# BitUDCounter.net
KiCad netlist of a schematic drawn in EAGLE
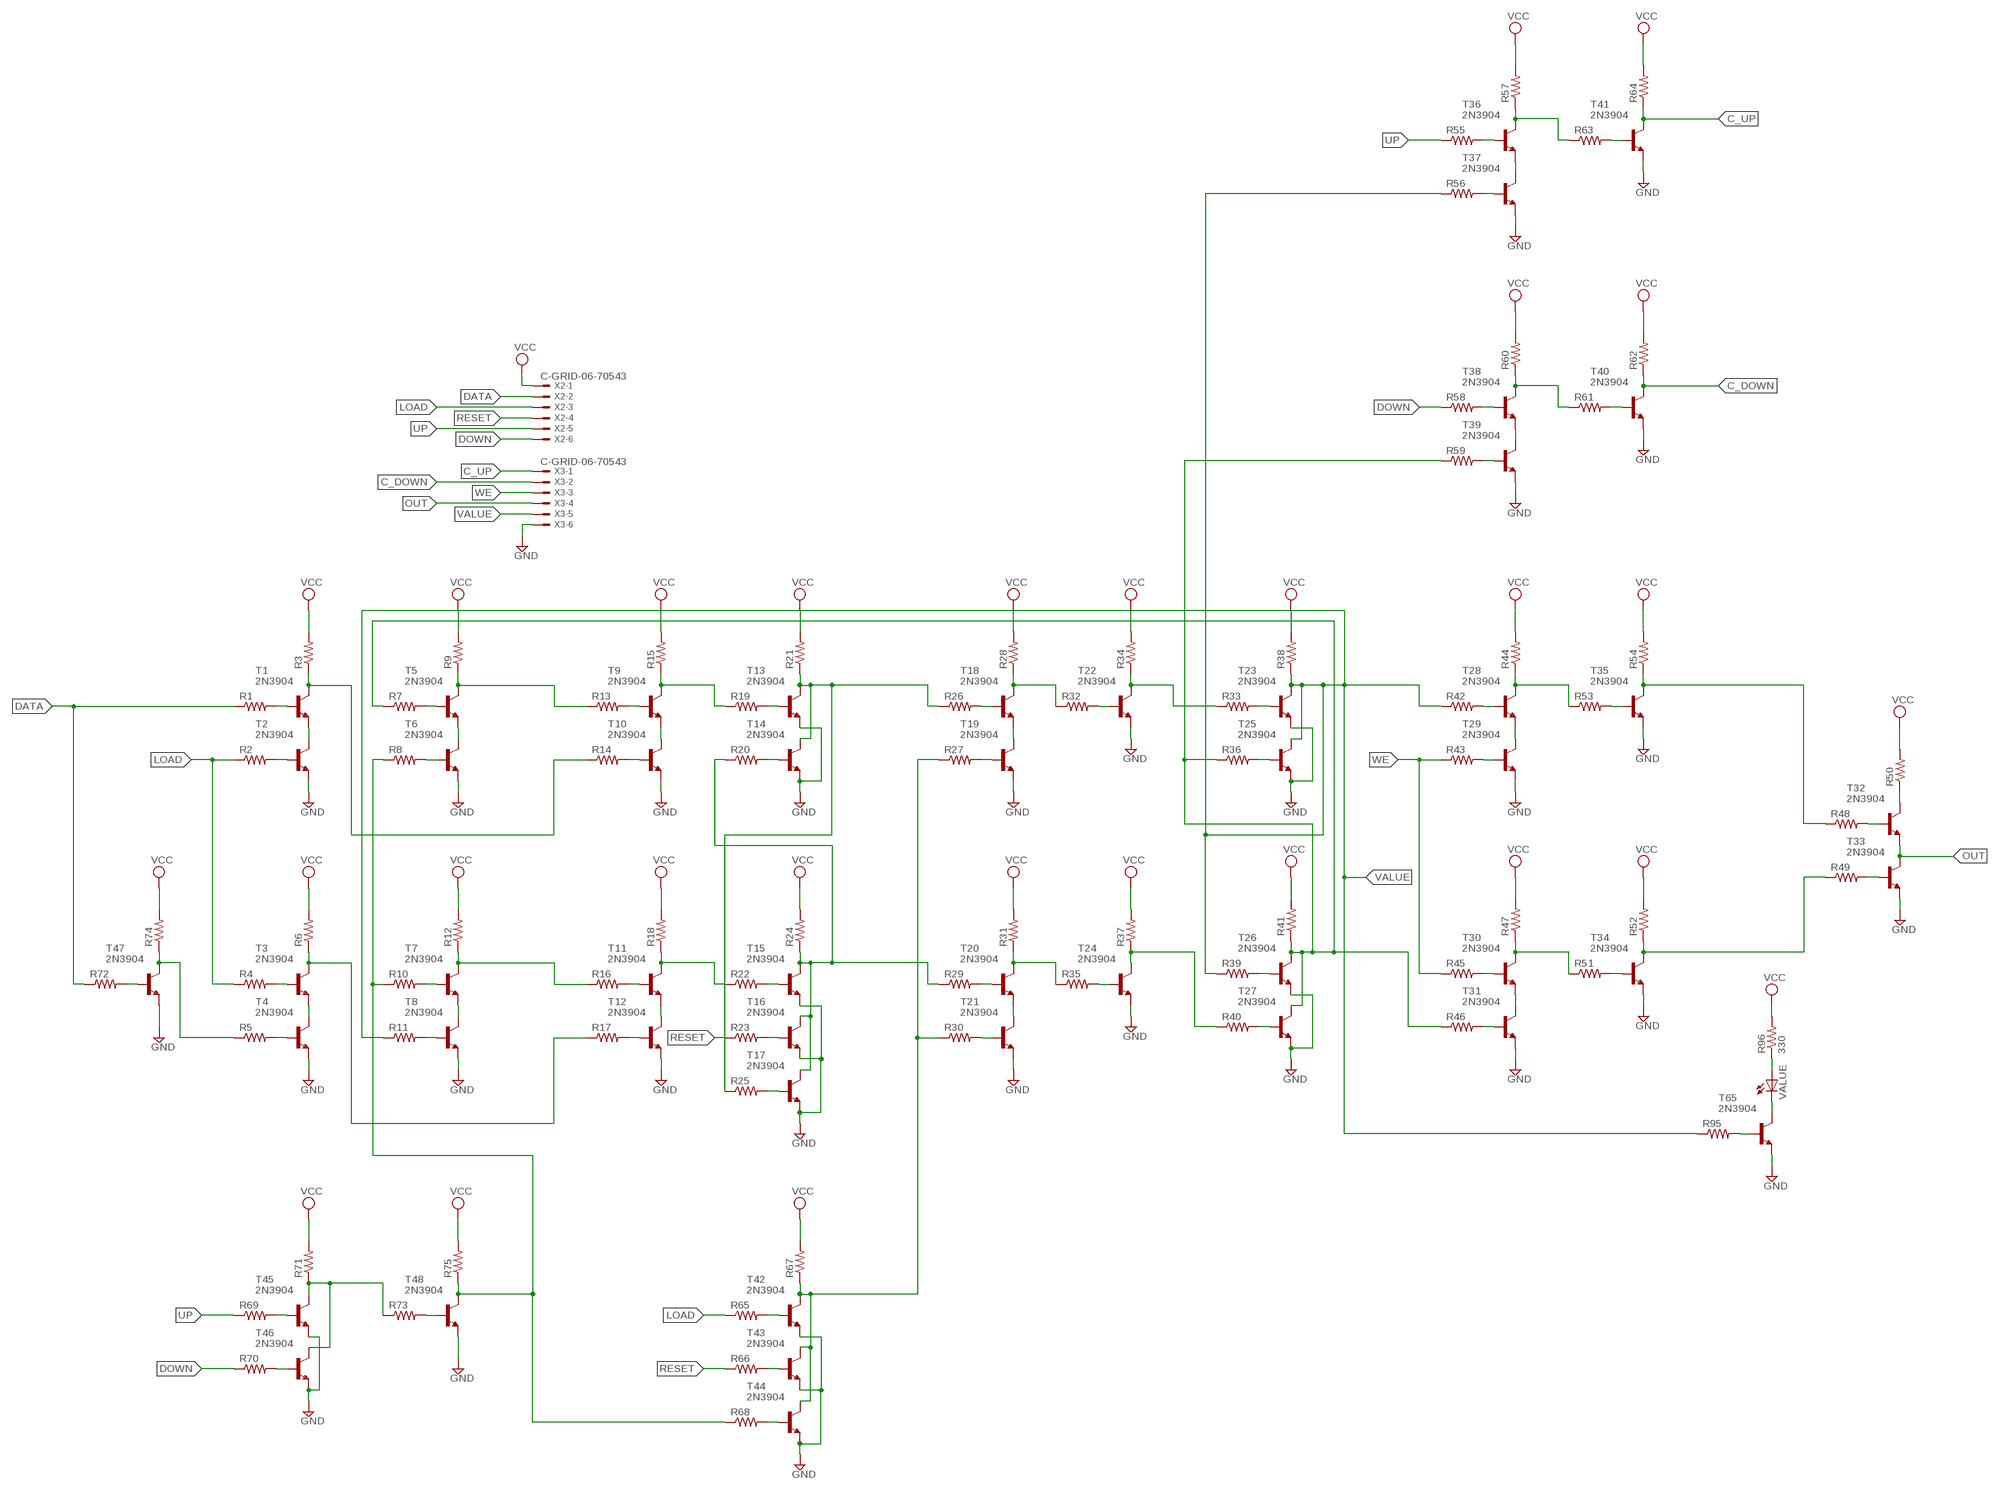
[diagram p0: schematic, sheet 1]

(export (version "E")
  (design (tool "Eeschema 10.0.6"))
  (components
    (comp (ref "R1")
      (value "R-US_0309/10")
      (footprint "eagle-import:0309_10")
      (libsource (lib "eagle-import") (part "R-US_0309/10"))
    )
    (comp (ref "R2")
      (value "R-US_0309/10")
      (footprint "eagle-import:0309_10")
      (libsource (lib "eagle-import") (part "R-US_0309/10"))
    )
    (comp (ref "R3")
      (value "R-US_0309/10")
      (footprint "eagle-import:0309_10")
      (libsource (lib "eagle-import") (part "R-US_0309/10"))
    )
    (comp (ref "R4")
      (value "R-US_0309/10")
      (footprint "eagle-import:0309_10")
      (libsource (lib "eagle-import") (part "R-US_0309/10"))
    )
    (comp (ref "R5")
      (value "R-US_0309/10")
      (footprint "eagle-import:0309_10")
      (libsource (lib "eagle-import") (part "R-US_0309/10"))
    )
    (comp (ref "R6")
      (value "R-US_0309/10")
      (footprint "eagle-import:0309_10")
      (libsource (lib "eagle-import") (part "R-US_0309/10"))
    )
    (comp (ref "R7")
      (value "R-US_0309/10")
      (footprint "eagle-import:0309_10")
      (libsource (lib "eagle-import") (part "R-US_0309/10"))
    )
    (comp (ref "R8")
      (value "R-US_0309/10")
      (footprint "eagle-import:0309_10")
      (libsource (lib "eagle-import") (part "R-US_0309/10"))
    )
    (comp (ref "R9")
      (value "R-US_0309/10")
      (footprint "eagle-import:0309_10")
      (libsource (lib "eagle-import") (part "R-US_0309/10"))
    )
    (comp (ref "R10")
      (value "R-US_0309/10")
      (footprint "eagle-import:0309_10")
      (libsource (lib "eagle-import") (part "R-US_0309/10"))
    )
    (comp (ref "R11")
      (value "R-US_0309/10")
      (footprint "eagle-import:0309_10")
      (libsource (lib "eagle-import") (part "R-US_0309/10"))
    )
    (comp (ref "R12")
      (value "R-US_0309/10")
      (footprint "eagle-import:0309_10")
      (libsource (lib "eagle-import") (part "R-US_0309/10"))
    )
    (comp (ref "R13")
      (value "R-US_0309/10")
      (footprint "eagle-import:0309_10")
      (libsource (lib "eagle-import") (part "R-US_0309/10"))
    )
    (comp (ref "R14")
      (value "R-US_0309/10")
      (footprint "eagle-import:0309_10")
      (libsource (lib "eagle-import") (part "R-US_0309/10"))
    )
    (comp (ref "R15")
      (value "R-US_0309/10")
      (footprint "eagle-import:0309_10")
      (libsource (lib "eagle-import") (part "R-US_0309/10"))
    )
    (comp (ref "R16")
      (value "R-US_0309/10")
      (footprint "eagle-import:0309_10")
      (libsource (lib "eagle-import") (part "R-US_0309/10"))
    )
    (comp (ref "R17")
      (value "R-US_0309/10")
      (footprint "eagle-import:0309_10")
      (libsource (lib "eagle-import") (part "R-US_0309/10"))
    )
    (comp (ref "R18")
      (value "R-US_0309/10")
      (footprint "eagle-import:0309_10")
      (libsource (lib "eagle-import") (part "R-US_0309/10"))
    )
    (comp (ref "R19")
      (value "R-US_0309/10")
      (footprint "eagle-import:0309_10")
      (libsource (lib "eagle-import") (part "R-US_0309/10"))
    )
    (comp (ref "R20")
      (value "R-US_0309/10")
      (footprint "eagle-import:0309_10")
      (libsource (lib "eagle-import") (part "R-US_0309/10"))
    )
    (comp (ref "R21")
      (value "R-US_0309/10")
      (footprint "eagle-import:0309_10")
      (libsource (lib "eagle-import") (part "R-US_0309/10"))
    )
    (comp (ref "R22")
      (value "R-US_0309/10")
      (footprint "eagle-import:0309_10")
      (libsource (lib "eagle-import") (part "R-US_0309/10"))
    )
    (comp (ref "R23")
      (value "R-US_0309/10")
      (footprint "eagle-import:0309_10")
      (libsource (lib "eagle-import") (part "R-US_0309/10"))
    )
    (comp (ref "R24")
      (value "R-US_0309/10")
      (footprint "eagle-import:0309_10")
      (libsource (lib "eagle-import") (part "R-US_0309/10"))
    )
    (comp (ref "R25")
      (value "R-US_0309/10")
      (footprint "eagle-import:0309_10")
      (libsource (lib "eagle-import") (part "R-US_0309/10"))
    )
    (comp (ref "R26")
      (value "R-US_0309/10")
      (footprint "eagle-import:0309_10")
      (libsource (lib "eagle-import") (part "R-US_0309/10"))
    )
    (comp (ref "R27")
      (value "R-US_0309/10")
      (footprint "eagle-import:0309_10")
      (libsource (lib "eagle-import") (part "R-US_0309/10"))
    )
    (comp (ref "R28")
      (value "R-US_0309/10")
      (footprint "eagle-import:0309_10")
      (libsource (lib "eagle-import") (part "R-US_0309/10"))
    )
    (comp (ref "R29")
      (value "R-US_0309/10")
      (footprint "eagle-import:0309_10")
      (libsource (lib "eagle-import") (part "R-US_0309/10"))
    )
    (comp (ref "R30")
      (value "R-US_0309/10")
      (footprint "eagle-import:0309_10")
      (libsource (lib "eagle-import") (part "R-US_0309/10"))
    )
    (comp (ref "R31")
      (value "R-US_0309/10")
      (footprint "eagle-import:0309_10")
      (libsource (lib "eagle-import") (part "R-US_0309/10"))
    )
    (comp (ref "R32")
      (value "R-US_0309/10")
      (footprint "eagle-import:0309_10")
      (libsource (lib "eagle-import") (part "R-US_0309/10"))
    )
    (comp (ref "R33")
      (value "R-US_0309/10")
      (footprint "eagle-import:0309_10")
      (libsource (lib "eagle-import") (part "R-US_0309/10"))
    )
    (comp (ref "R34")
      (value "R-US_0309/10")
      (footprint "eagle-import:0309_10")
      (libsource (lib "eagle-import") (part "R-US_0309/10"))
    )
    (comp (ref "R35")
      (value "R-US_0309/10")
      (footprint "eagle-import:0309_10")
      (libsource (lib "eagle-import") (part "R-US_0309/10"))
    )
    (comp (ref "R36")
      (value "R-US_0309/10")
      (footprint "eagle-import:0309_10")
      (libsource (lib "eagle-import") (part "R-US_0309/10"))
    )
    (comp (ref "R37")
      (value "R-US_0309/10")
      (footprint "eagle-import:0309_10")
      (libsource (lib "eagle-import") (part "R-US_0309/10"))
    )
    (comp (ref "R38")
      (value "R-US_0309/10")
      (footprint "eagle-import:0309_10")
      (libsource (lib "eagle-import") (part "R-US_0309/10"))
    )
    (comp (ref "R39")
      (value "R-US_0309/10")
      (footprint "eagle-import:0309_10")
      (libsource (lib "eagle-import") (part "R-US_0309/10"))
    )
    (comp (ref "R40")
      (value "R-US_0309/10")
      (footprint "eagle-import:0309_10")
      (libsource (lib "eagle-import") (part "R-US_0309/10"))
    )
    (comp (ref "R41")
      (value "R-US_0309/10")
      (footprint "eagle-import:0309_10")
      (libsource (lib "eagle-import") (part "R-US_0309/10"))
    )
    (comp (ref "R42")
      (value "R-US_0309/10")
      (footprint "eagle-import:0309_10")
      (libsource (lib "eagle-import") (part "R-US_0309/10"))
    )
    (comp (ref "R43")
      (value "R-US_0309/10")
      (footprint "eagle-import:0309_10")
      (libsource (lib "eagle-import") (part "R-US_0309/10"))
    )
    (comp (ref "R44")
      (value "R-US_0309/10")
      (footprint "eagle-import:0309_10")
      (libsource (lib "eagle-import") (part "R-US_0309/10"))
    )
    (comp (ref "R45")
      (value "R-US_0309/10")
      (footprint "eagle-import:0309_10")
      (libsource (lib "eagle-import") (part "R-US_0309/10"))
    )
    (comp (ref "R46")
      (value "R-US_0309/10")
      (footprint "eagle-import:0309_10")
      (libsource (lib "eagle-import") (part "R-US_0309/10"))
    )
    (comp (ref "R47")
      (value "R-US_0309/10")
      (footprint "eagle-import:0309_10")
      (libsource (lib "eagle-import") (part "R-US_0309/10"))
    )
    (comp (ref "R48")
      (value "R-US_0309/10")
      (footprint "eagle-import:0309_10")
      (libsource (lib "eagle-import") (part "R-US_0309/10"))
    )
    (comp (ref "R49")
      (value "R-US_0309/10")
      (footprint "eagle-import:0309_10")
      (libsource (lib "eagle-import") (part "R-US_0309/10"))
    )
    (comp (ref "R50")
      (value "R-US_0309/10")
      (footprint "eagle-import:0309_10")
      (libsource (lib "eagle-import") (part "R-US_0309/10"))
    )
    (comp (ref "R51")
      (value "R-US_0309/10")
      (footprint "eagle-import:0309_10")
      (libsource (lib "eagle-import") (part "R-US_0309/10"))
    )
    (comp (ref "R52")
      (value "R-US_0309/10")
      (footprint "eagle-import:0309_10")
      (libsource (lib "eagle-import") (part "R-US_0309/10"))
    )
    (comp (ref "R53")
      (value "R-US_0309/10")
      (footprint "eagle-import:0309_10")
      (libsource (lib "eagle-import") (part "R-US_0309/10"))
    )
    (comp (ref "R54")
      (value "R-US_0309/10")
      (footprint "eagle-import:0309_10")
      (libsource (lib "eagle-import") (part "R-US_0309/10"))
    )
    (comp (ref "R55")
      (value "R-US_0309/10")
      (footprint "eagle-import:0309_10")
      (libsource (lib "eagle-import") (part "R-US_0309/10"))
    )
    (comp (ref "R56")
      (value "R-US_0309/10")
      (footprint "eagle-import:0309_10")
      (libsource (lib "eagle-import") (part "R-US_0309/10"))
    )
    (comp (ref "R57")
      (value "R-US_0309/10")
      (footprint "eagle-import:0309_10")
      (libsource (lib "eagle-import") (part "R-US_0309/10"))
    )
    (comp (ref "R58")
      (value "R-US_0309/10")
      (footprint "eagle-import:0309_10")
      (libsource (lib "eagle-import") (part "R-US_0309/10"))
    )
    (comp (ref "R59")
      (value "R-US_0309/10")
      (footprint "eagle-import:0309_10")
      (libsource (lib "eagle-import") (part "R-US_0309/10"))
    )
    (comp (ref "R60")
      (value "R-US_0309/10")
      (footprint "eagle-import:0309_10")
      (libsource (lib "eagle-import") (part "R-US_0309/10"))
    )
    (comp (ref "R61")
      (value "R-US_0309/10")
      (footprint "eagle-import:0309_10")
      (libsource (lib "eagle-import") (part "R-US_0309/10"))
    )
    (comp (ref "R62")
      (value "R-US_0309/10")
      (footprint "eagle-import:0309_10")
      (libsource (lib "eagle-import") (part "R-US_0309/10"))
    )
    (comp (ref "R63")
      (value "R-US_0309/10")
      (footprint "eagle-import:0309_10")
      (libsource (lib "eagle-import") (part "R-US_0309/10"))
    )
    (comp (ref "R64")
      (value "R-US_0309/10")
      (footprint "eagle-import:0309_10")
      (libsource (lib "eagle-import") (part "R-US_0309/10"))
    )
    (comp (ref "R65")
      (value "R-US_0309/10")
      (footprint "eagle-import:0309_10")
      (libsource (lib "eagle-import") (part "R-US_0309/10"))
    )
    (comp (ref "R66")
      (value "R-US_0309/10")
      (footprint "eagle-import:0309_10")
      (libsource (lib "eagle-import") (part "R-US_0309/10"))
    )
    (comp (ref "R67")
      (value "R-US_0309/10")
      (footprint "eagle-import:0309_10")
      (libsource (lib "eagle-import") (part "R-US_0309/10"))
    )
    (comp (ref "R68")
      (value "R-US_0309/10")
      (footprint "eagle-import:0309_10")
      (libsource (lib "eagle-import") (part "R-US_0309/10"))
    )
    (comp (ref "R69")
      (value "R-US_0309/10")
      (footprint "eagle-import:0309_10")
      (libsource (lib "eagle-import") (part "R-US_0309/10"))
    )
    (comp (ref "R70")
      (value "R-US_0309/10")
      (footprint "eagle-import:0309_10")
      (libsource (lib "eagle-import") (part "R-US_0309/10"))
    )
    (comp (ref "R71")
      (value "R-US_0309/10")
      (footprint "eagle-import:0309_10")
      (libsource (lib "eagle-import") (part "R-US_0309/10"))
    )
    (comp (ref "R72")
      (value "R-US_0309/10")
      (footprint "eagle-import:0309_10")
      (libsource (lib "eagle-import") (part "R-US_0309/10"))
    )
    (comp (ref "R73")
      (value "R-US_0309/10")
      (footprint "eagle-import:0309_10")
      (libsource (lib "eagle-import") (part "R-US_0309/10"))
    )
    (comp (ref "R74")
      (value "R-US_0309/10")
      (footprint "eagle-import:0309_10")
      (libsource (lib "eagle-import") (part "R-US_0309/10"))
    )
    (comp (ref "R75")
      (value "R-US_0309/10")
      (footprint "eagle-import:0309_10")
      (libsource (lib "eagle-import") (part "R-US_0309/10"))
    )
    (comp (ref "R95")
      (value "R-US_0309/10")
      (footprint "eagle-import:0309_10")
      (libsource (lib "eagle-import") (part "R-US_0309/10"))
    )
    (comp (ref "R96")
      (value "330")
      (footprint "eagle-import:0309_10")
      (libsource (lib "eagle-import") (part "R-US_0309/10"))
    )
    (comp (ref "T1")
      (value "2N3904")
      (footprint "eagle-import:TO92")
      (libsource (lib "eagle-import") (part "2N3904"))
    )
    (comp (ref "T2")
      (value "2N3904")
      (footprint "eagle-import:TO92")
      (libsource (lib "eagle-import") (part "2N3904"))
    )
    (comp (ref "T3")
      (value "2N3904")
      (footprint "eagle-import:TO92")
      (libsource (lib "eagle-import") (part "2N3904"))
    )
    (comp (ref "T4")
      (value "2N3904")
      (footprint "eagle-import:TO92")
      (libsource (lib "eagle-import") (part "2N3904"))
    )
    (comp (ref "T5")
      (value "2N3904")
      (footprint "eagle-import:TO92")
      (libsource (lib "eagle-import") (part "2N3904"))
    )
    (comp (ref "T6")
      (value "2N3904")
      (footprint "eagle-import:TO92")
      (libsource (lib "eagle-import") (part "2N3904"))
    )
    (comp (ref "T7")
      (value "2N3904")
      (footprint "eagle-import:TO92")
      (libsource (lib "eagle-import") (part "2N3904"))
    )
    (comp (ref "T8")
      (value "2N3904")
      (footprint "eagle-import:TO92")
      (libsource (lib "eagle-import") (part "2N3904"))
    )
    (comp (ref "T9")
      (value "2N3904")
      (footprint "eagle-import:TO92")
      (libsource (lib "eagle-import") (part "2N3904"))
    )
    (comp (ref "T10")
      (value "2N3904")
      (footprint "eagle-import:TO92")
      (libsource (lib "eagle-import") (part "2N3904"))
    )
    (comp (ref "T11")
      (value "2N3904")
      (footprint "eagle-import:TO92")
      (libsource (lib "eagle-import") (part "2N3904"))
    )
    (comp (ref "T12")
      (value "2N3904")
      (footprint "eagle-import:TO92")
      (libsource (lib "eagle-import") (part "2N3904"))
    )
    (comp (ref "T13")
      (value "2N3904")
      (footprint "eagle-import:TO92")
      (libsource (lib "eagle-import") (part "2N3904"))
    )
    (comp (ref "T14")
      (value "2N3904")
      (footprint "eagle-import:TO92")
      (libsource (lib "eagle-import") (part "2N3904"))
    )
    (comp (ref "T15")
      (value "2N3904")
      (footprint "eagle-import:TO92")
      (libsource (lib "eagle-import") (part "2N3904"))
    )
    (comp (ref "T16")
      (value "2N3904")
      (footprint "eagle-import:TO92")
      (libsource (lib "eagle-import") (part "2N3904"))
    )
    (comp (ref "T17")
      (value "2N3904")
      (footprint "eagle-import:TO92")
      (libsource (lib "eagle-import") (part "2N3904"))
    )
    (comp (ref "T18")
      (value "2N3904")
      (footprint "eagle-import:TO92")
      (libsource (lib "eagle-import") (part "2N3904"))
    )
    (comp (ref "T19")
      (value "2N3904")
      (footprint "eagle-import:TO92")
      (libsource (lib "eagle-import") (part "2N3904"))
    )
    (comp (ref "T20")
      (value "2N3904")
      (footprint "eagle-import:TO92")
      (libsource (lib "eagle-import") (part "2N3904"))
    )
    (comp (ref "T21")
      (value "2N3904")
      (footprint "eagle-import:TO92")
      (libsource (lib "eagle-import") (part "2N3904"))
    )
    (comp (ref "T22")
      (value "2N3904")
      (footprint "eagle-import:TO92")
      (libsource (lib "eagle-import") (part "2N3904"))
    )
    (comp (ref "T23")
      (value "2N3904")
      (footprint "eagle-import:TO92")
      (libsource (lib "eagle-import") (part "2N3904"))
    )
    (comp (ref "T24")
      (value "2N3904")
      (footprint "eagle-import:TO92")
      (libsource (lib "eagle-import") (part "2N3904"))
    )
    (comp (ref "T25")
      (value "2N3904")
      (footprint "eagle-import:TO92")
      (libsource (lib "eagle-import") (part "2N3904"))
    )
    (comp (ref "T26")
      (value "2N3904")
      (footprint "eagle-import:TO92")
      (libsource (lib "eagle-import") (part "2N3904"))
    )
    (comp (ref "T27")
      (value "2N3904")
      (footprint "eagle-import:TO92")
      (libsource (lib "eagle-import") (part "2N3904"))
    )
    (comp (ref "T28")
      (value "2N3904")
      (footprint "eagle-import:TO92")
      (libsource (lib "eagle-import") (part "2N3904"))
    )
    (comp (ref "T29")
      (value "2N3904")
      (footprint "eagle-import:TO92")
      (libsource (lib "eagle-import") (part "2N3904"))
    )
    (comp (ref "T30")
      (value "2N3904")
      (footprint "eagle-import:TO92")
      (libsource (lib "eagle-import") (part "2N3904"))
    )
    (comp (ref "T31")
      (value "2N3904")
      (footprint "eagle-import:TO92")
      (libsource (lib "eagle-import") (part "2N3904"))
    )
    (comp (ref "T32")
      (value "2N3904")
      (footprint "eagle-import:TO92")
      (libsource (lib "eagle-import") (part "2N3904"))
    )
    (comp (ref "T33")
      (value "2N3904")
      (footprint "eagle-import:TO92")
      (libsource (lib "eagle-import") (part "2N3904"))
    )
    (comp (ref "T34")
      (value "2N3904")
      (footprint "eagle-import:TO92")
      (libsource (lib "eagle-import") (part "2N3904"))
    )
    (comp (ref "T35")
      (value "2N3904")
      (footprint "eagle-import:TO92")
      (libsource (lib "eagle-import") (part "2N3904"))
    )
    (comp (ref "T36")
      (value "2N3904")
      (footprint "eagle-import:TO92")
      (libsource (lib "eagle-import") (part "2N3904"))
    )
    (comp (ref "T37")
      (value "2N3904")
      (footprint "eagle-import:TO92")
      (libsource (lib "eagle-import") (part "2N3904"))
    )
    (comp (ref "T38")
      (value "2N3904")
      (footprint "eagle-import:TO92")
      (libsource (lib "eagle-import") (part "2N3904"))
    )
    (comp (ref "T39")
      (value "2N3904")
      (footprint "eagle-import:TO92")
      (libsource (lib "eagle-import") (part "2N3904"))
    )
    (comp (ref "T40")
      (value "2N3904")
      (footprint "eagle-import:TO92")
      (libsource (lib "eagle-import") (part "2N3904"))
    )
    (comp (ref "T41")
      (value "2N3904")
      (footprint "eagle-import:TO92")
      (libsource (lib "eagle-import") (part "2N3904"))
    )
    (comp (ref "T42")
      (value "2N3904")
      (footprint "eagle-import:TO92")
      (libsource (lib "eagle-import") (part "2N3904"))
    )
    (comp (ref "T43")
      (value "2N3904")
      (footprint "eagle-import:TO92")
      (libsource (lib "eagle-import") (part "2N3904"))
    )
    (comp (ref "T44")
      (value "2N3904")
      (footprint "eagle-import:TO92")
      (libsource (lib "eagle-import") (part "2N3904"))
    )
    (comp (ref "T45")
      (value "2N3904")
      (footprint "eagle-import:TO92")
      (libsource (lib "eagle-import") (part "2N3904"))
    )
    (comp (ref "T46")
      (value "2N3904")
      (footprint "eagle-import:TO92")
      (libsource (lib "eagle-import") (part "2N3904"))
    )
    (comp (ref "T47")
      (value "2N3904")
      (footprint "eagle-import:TO92")
      (libsource (lib "eagle-import") (part "2N3904"))
    )
    (comp (ref "T48")
      (value "2N3904")
      (footprint "eagle-import:TO92")
      (libsource (lib "eagle-import") (part "2N3904"))
    )
    (comp (ref "T65")
      (value "2N3904")
      (footprint "eagle-import:TO92")
      (libsource (lib "eagle-import") (part "2N3904"))
    )
    (comp (ref "VALUE")
      (value "LED5MM")
      (footprint "eagle-import:LED5MM")
      (libsource (lib "eagle-import") (part "LED5MM"))
    )
    (comp (ref "X2")
      (value "C-GRID-06-70543")
      (footprint "eagle-import:70543-06")
      (fields (field (name "MF") "MOLEX"))
      (libsource (lib "eagle-import") (part "C-GRID-06-70543"))
    )
    (comp (ref "X3")
      (value "C-GRID-06-70543")
      (footprint "eagle-import:70543-06")
      (fields (field (name "MF") "MOLEX"))
      (libsource (lib "eagle-import") (part "C-GRID-06-70543"))
    )
  )
  (nets
    (net (code "1") (name "C_DOWN") (class "Default")
      (node (ref "R62") (pin "1") (pinfunction "1_1") (pintype "passive"))
      (node (ref "T40") (pin "1") (pinfunction "C_1") (pintype "passive"))
      (node (ref "X3") (pin "2") (pinfunction "S_2") (pintype "passive"))
    )
    (net (code "2") (name "C_UP") (class "Default")
      (node (ref "R64") (pin "1") (pinfunction "1_1") (pintype "passive"))
      (node (ref "T41") (pin "1") (pinfunction "C_1") (pintype "passive"))
      (node (ref "X3") (pin "1") (pinfunction "S_1") (pintype "passive"))
    )
    (net (code "3") (name "DATA") (class "Default")
      (node (ref "R1") (pin "1") (pinfunction "1_1") (pintype "passive"))
      (node (ref "R72") (pin "1") (pinfunction "1_1") (pintype "passive"))
      (node (ref "X2") (pin "2") (pinfunction "S_2") (pintype "passive"))
    )
    (net (code "4") (name "DOWN") (class "Default")
      (node (ref "R58") (pin "1") (pinfunction "1_1") (pintype "passive"))
      (node (ref "R70") (pin "1") (pinfunction "1_1") (pintype "passive"))
      (node (ref "X2") (pin "6") (pinfunction "S_6") (pintype "passive"))
    )
    (net (code "5") (name "GND") (class "Default")
      (node (ref "T10") (pin "3") (pinfunction "E_3") (pintype "passive"))
      (node (ref "T12") (pin "3") (pinfunction "E_3") (pintype "passive"))
      (node (ref "T13") (pin "3") (pinfunction "E_3") (pintype "passive"))
      (node (ref "T14") (pin "3") (pinfunction "E_3") (pintype "passive"))
      (node (ref "T15") (pin "3") (pinfunction "E_3") (pintype "passive"))
      (node (ref "T16") (pin "3") (pinfunction "E_3") (pintype "passive"))
      (node (ref "T17") (pin "3") (pinfunction "E_3") (pintype "passive"))
      (node (ref "T19") (pin "3") (pinfunction "E_3") (pintype "passive"))
      (node (ref "T2") (pin "3") (pinfunction "E_3") (pintype "passive"))
      (node (ref "T21") (pin "3") (pinfunction "E_3") (pintype "passive"))
      (node (ref "T22") (pin "3") (pinfunction "E_3") (pintype "passive"))
      (node (ref "T23") (pin "3") (pinfunction "E_3") (pintype "passive"))
      (node (ref "T24") (pin "3") (pinfunction "E_3") (pintype "passive"))
      (node (ref "T25") (pin "3") (pinfunction "E_3") (pintype "passive"))
      (node (ref "T26") (pin "3") (pinfunction "E_3") (pintype "passive"))
      (node (ref "T27") (pin "3") (pinfunction "E_3") (pintype "passive"))
      (node (ref "T29") (pin "3") (pinfunction "E_3") (pintype "passive"))
      (node (ref "T31") (pin "3") (pinfunction "E_3") (pintype "passive"))
      (node (ref "T33") (pin "3") (pinfunction "E_3") (pintype "passive"))
      (node (ref "T34") (pin "3") (pinfunction "E_3") (pintype "passive"))
      (node (ref "T35") (pin "3") (pinfunction "E_3") (pintype "passive"))
      (node (ref "T37") (pin "3") (pinfunction "E_3") (pintype "passive"))
      (node (ref "T39") (pin "3") (pinfunction "E_3") (pintype "passive"))
      (node (ref "T4") (pin "3") (pinfunction "E_3") (pintype "passive"))
      (node (ref "T40") (pin "3") (pinfunction "E_3") (pintype "passive"))
      (node (ref "T41") (pin "3") (pinfunction "E_3") (pintype "passive"))
      (node (ref "T42") (pin "3") (pinfunction "E_3") (pintype "passive"))
      (node (ref "T43") (pin "3") (pinfunction "E_3") (pintype "passive"))
      (node (ref "T44") (pin "3") (pinfunction "E_3") (pintype "passive"))
      (node (ref "T45") (pin "3") (pinfunction "E_3") (pintype "passive"))
      (node (ref "T46") (pin "3") (pinfunction "E_3") (pintype "passive"))
      (node (ref "T47") (pin "3") (pinfunction "E_3") (pintype "passive"))
      (node (ref "T48") (pin "3") (pinfunction "E_3") (pintype "passive"))
      (node (ref "T6") (pin "3") (pinfunction "E_3") (pintype "passive"))
      (node (ref "T65") (pin "3") (pinfunction "E_3") (pintype "passive"))
      (node (ref "T8") (pin "3") (pinfunction "E_3") (pintype "passive"))
      (node (ref "X3") (pin "6") (pinfunction "S_6") (pintype "passive"))
    )
    (net (code "6") (name "LOAD") (class "Default")
      (node (ref "R2") (pin "1") (pinfunction "1_1") (pintype "passive"))
      (node (ref "R4") (pin "1") (pinfunction "1_1") (pintype "passive"))
      (node (ref "R65") (pin "1") (pinfunction "1_1") (pintype "passive"))
      (node (ref "X2") (pin "3") (pinfunction "S_3") (pintype "passive"))
    )
    (net (code "7") (name "Net-(R96-Pad1)") (class "Default")
      (node (ref "R96") (pin "1") (pinfunction "1_1") (pintype "passive"))
      (node (ref "VALUE") (pin "A") (pinfunction "A_A") (pintype "passive"))
    )
    (net (code "8") (name "Net-(T1-B)") (class "Default")
      (node (ref "R1") (pin "2") (pinfunction "2_2") (pintype "passive"))
      (node (ref "T1") (pin "2") (pinfunction "B_2") (pintype "passive"))
    )
    (net (code "9") (name "Net-(T1-C)") (class "Default")
      (node (ref "R14") (pin "1") (pinfunction "1_1") (pintype "passive"))
      (node (ref "R3") (pin "1") (pinfunction "1_1") (pintype "passive"))
      (node (ref "T1") (pin "1") (pinfunction "C_1") (pintype "passive"))
    )
    (net (code "10") (name "Net-(T1-E)") (class "Default")
      (node (ref "T1") (pin "3") (pinfunction "E_3") (pintype "passive"))
      (node (ref "T2") (pin "1") (pinfunction "C_1") (pintype "passive"))
    )
    (net (code "11") (name "Net-(T2-B)") (class "Default")
      (node (ref "R2") (pin "2") (pinfunction "2_2") (pintype "passive"))
      (node (ref "T2") (pin "2") (pinfunction "B_2") (pintype "passive"))
    )
    (net (code "12") (name "Net-(T3-B)") (class "Default")
      (node (ref "R4") (pin "2") (pinfunction "2_2") (pintype "passive"))
      (node (ref "T3") (pin "2") (pinfunction "B_2") (pintype "passive"))
    )
    (net (code "13") (name "Net-(T3-C)") (class "Default")
      (node (ref "R17") (pin "1") (pinfunction "1_1") (pintype "passive"))
      (node (ref "R6") (pin "1") (pinfunction "1_1") (pintype "passive"))
      (node (ref "T3") (pin "1") (pinfunction "C_1") (pintype "passive"))
    )
    (net (code "14") (name "Net-(T3-E)") (class "Default")
      (node (ref "T3") (pin "3") (pinfunction "E_3") (pintype "passive"))
      (node (ref "T4") (pin "1") (pinfunction "C_1") (pintype "passive"))
    )
    (net (code "15") (name "Net-(T4-B)") (class "Default")
      (node (ref "R5") (pin "2") (pinfunction "2_2") (pintype "passive"))
      (node (ref "T4") (pin "2") (pinfunction "B_2") (pintype "passive"))
    )
    (net (code "16") (name "Net-(T5-B)") (class "Default")
      (node (ref "R7") (pin "2") (pinfunction "2_2") (pintype "passive"))
      (node (ref "T5") (pin "2") (pinfunction "B_2") (pintype "passive"))
    )
    (net (code "17") (name "Net-(T5-C)") (class "Default")
      (node (ref "R13") (pin "1") (pinfunction "1_1") (pintype "passive"))
      (node (ref "R9") (pin "1") (pinfunction "1_1") (pintype "passive"))
      (node (ref "T5") (pin "1") (pinfunction "C_1") (pintype "passive"))
    )
    (net (code "18") (name "Net-(T5-E)") (class "Default")
      (node (ref "T5") (pin "3") (pinfunction "E_3") (pintype "passive"))
      (node (ref "T6") (pin "1") (pinfunction "C_1") (pintype "passive"))
    )
    (net (code "19") (name "Net-(T6-B)") (class "Default")
      (node (ref "R8") (pin "2") (pinfunction "2_2") (pintype "passive"))
      (node (ref "T6") (pin "2") (pinfunction "B_2") (pintype "passive"))
    )
    (net (code "20") (name "Net-(T7-B)") (class "Default")
      (node (ref "R10") (pin "2") (pinfunction "2_2") (pintype "passive"))
      (node (ref "T7") (pin "2") (pinfunction "B_2") (pintype "passive"))
    )
    (net (code "21") (name "Net-(T7-C)") (class "Default")
      (node (ref "R12") (pin "1") (pinfunction "1_1") (pintype "passive"))
      (node (ref "R16") (pin "1") (pinfunction "1_1") (pintype "passive"))
      (node (ref "T7") (pin "1") (pinfunction "C_1") (pintype "passive"))
    )
    (net (code "22") (name "Net-(T7-E)") (class "Default")
      (node (ref "T7") (pin "3") (pinfunction "E_3") (pintype "passive"))
      (node (ref "T8") (pin "1") (pinfunction "C_1") (pintype "passive"))
    )
    (net (code "23") (name "Net-(T8-B)") (class "Default")
      (node (ref "R11") (pin "2") (pinfunction "2_2") (pintype "passive"))
      (node (ref "T8") (pin "2") (pinfunction "B_2") (pintype "passive"))
    )
    (net (code "24") (name "Net-(T9-B)") (class "Default")
      (node (ref "R13") (pin "2") (pinfunction "2_2") (pintype "passive"))
      (node (ref "T9") (pin "2") (pinfunction "B_2") (pintype "passive"))
    )
    (net (code "25") (name "Net-(T9-C)") (class "Default")
      (node (ref "R15") (pin "1") (pinfunction "1_1") (pintype "passive"))
      (node (ref "R19") (pin "1") (pinfunction "1_1") (pintype "passive"))
      (node (ref "T9") (pin "1") (pinfunction "C_1") (pintype "passive"))
    )
    (net (code "26") (name "Net-(T10-B)") (class "Default")
      (node (ref "R14") (pin "2") (pinfunction "2_2") (pintype "passive"))
      (node (ref "T10") (pin "2") (pinfunction "B_2") (pintype "passive"))
    )
    (net (code "27") (name "Net-(T10-C)") (class "Default")
      (node (ref "T10") (pin "1") (pinfunction "C_1") (pintype "passive"))
      (node (ref "T9") (pin "3") (pinfunction "E_3") (pintype "passive"))
    )
    (net (code "28") (name "Net-(T11-B)") (class "Default")
      (node (ref "R16") (pin "2") (pinfunction "2_2") (pintype "passive"))
      (node (ref "T11") (pin "2") (pinfunction "B_2") (pintype "passive"))
    )
    (net (code "29") (name "Net-(T11-C)") (class "Default")
      (node (ref "R18") (pin "1") (pinfunction "1_1") (pintype "passive"))
      (node (ref "R22") (pin "1") (pinfunction "1_1") (pintype "passive"))
      (node (ref "T11") (pin "1") (pinfunction "C_1") (pintype "passive"))
    )
    (net (code "30") (name "Net-(T11-E)") (class "Default")
      (node (ref "T11") (pin "3") (pinfunction "E_3") (pintype "passive"))
      (node (ref "T12") (pin "1") (pinfunction "C_1") (pintype "passive"))
    )
    (net (code "31") (name "Net-(T12-B)") (class "Default")
      (node (ref "R17") (pin "2") (pinfunction "2_2") (pintype "passive"))
      (node (ref "T12") (pin "2") (pinfunction "B_2") (pintype "passive"))
    )
    (net (code "32") (name "Net-(T13-B)") (class "Default")
      (node (ref "R19") (pin "2") (pinfunction "2_2") (pintype "passive"))
      (node (ref "T13") (pin "2") (pinfunction "B_2") (pintype "passive"))
    )
    (net (code "33") (name "Net-(T13-C)") (class "Default")
      (node (ref "R21") (pin "1") (pinfunction "1_1") (pintype "passive"))
      (node (ref "R25") (pin "1") (pinfunction "1_1") (pintype "passive"))
      (node (ref "R26") (pin "1") (pinfunction "1_1") (pintype "passive"))
      (node (ref "T13") (pin "1") (pinfunction "C_1") (pintype "passive"))
      (node (ref "T14") (pin "1") (pinfunction "C_1") (pintype "passive"))
    )
    (net (code "34") (name "Net-(T14-B)") (class "Default")
      (node (ref "R20") (pin "2") (pinfunction "2_2") (pintype "passive"))
      (node (ref "T14") (pin "2") (pinfunction "B_2") (pintype "passive"))
    )
    (net (code "35") (name "Net-(T15-B)") (class "Default")
      (node (ref "R22") (pin "2") (pinfunction "2_2") (pintype "passive"))
      (node (ref "T15") (pin "2") (pinfunction "B_2") (pintype "passive"))
    )
    (net (code "36") (name "Net-(T15-C)") (class "Default")
      (node (ref "R20") (pin "1") (pinfunction "1_1") (pintype "passive"))
      (node (ref "R24") (pin "1") (pinfunction "1_1") (pintype "passive"))
      (node (ref "R29") (pin "1") (pinfunction "1_1") (pintype "passive"))
      (node (ref "T15") (pin "1") (pinfunction "C_1") (pintype "passive"))
      (node (ref "T16") (pin "1") (pinfunction "C_1") (pintype "passive"))
      (node (ref "T17") (pin "1") (pinfunction "C_1") (pintype "passive"))
    )
    (net (code "37") (name "Net-(T16-B)") (class "Default")
      (node (ref "R23") (pin "2") (pinfunction "2_2") (pintype "passive"))
      (node (ref "T16") (pin "2") (pinfunction "B_2") (pintype "passive"))
    )
    (net (code "38") (name "Net-(T17-B)") (class "Default")
      (node (ref "R25") (pin "2") (pinfunction "2_2") (pintype "passive"))
      (node (ref "T17") (pin "2") (pinfunction "B_2") (pintype "passive"))
    )
    (net (code "39") (name "Net-(T18-B)") (class "Default")
      (node (ref "R26") (pin "2") (pinfunction "2_2") (pintype "passive"))
      (node (ref "T18") (pin "2") (pinfunction "B_2") (pintype "passive"))
    )
    (net (code "40") (name "Net-(T18-C)") (class "Default")
      (node (ref "R28") (pin "1") (pinfunction "1_1") (pintype "passive"))
      (node (ref "R32") (pin "1") (pinfunction "1_1") (pintype "passive"))
      (node (ref "T18") (pin "1") (pinfunction "C_1") (pintype "passive"))
    )
    (net (code "41") (name "Net-(T18-E)") (class "Default")
      (node (ref "T18") (pin "3") (pinfunction "E_3") (pintype "passive"))
      (node (ref "T19") (pin "1") (pinfunction "C_1") (pintype "passive"))
    )
    (net (code "42") (name "Net-(T19-B)") (class "Default")
      (node (ref "R27") (pin "2") (pinfunction "2_2") (pintype "passive"))
      (node (ref "T19") (pin "2") (pinfunction "B_2") (pintype "passive"))
    )
    (net (code "43") (name "Net-(T20-B)") (class "Default")
      (node (ref "R29") (pin "2") (pinfunction "2_2") (pintype "passive"))
      (node (ref "T20") (pin "2") (pinfunction "B_2") (pintype "passive"))
    )
    (net (code "44") (name "Net-(T20-C)") (class "Default")
      (node (ref "R31") (pin "1") (pinfunction "1_1") (pintype "passive"))
      (node (ref "R35") (pin "1") (pinfunction "1_1") (pintype "passive"))
      (node (ref "T20") (pin "1") (pinfunction "C_1") (pintype "passive"))
    )
    (net (code "45") (name "Net-(T20-E)") (class "Default")
      (node (ref "T20") (pin "3") (pinfunction "E_3") (pintype "passive"))
      (node (ref "T21") (pin "1") (pinfunction "C_1") (pintype "passive"))
    )
    (net (code "46") (name "Net-(T21-B)") (class "Default")
      (node (ref "R30") (pin "2") (pinfunction "2_2") (pintype "passive"))
      (node (ref "T21") (pin "2") (pinfunction "B_2") (pintype "passive"))
    )
    (net (code "47") (name "Net-(T22-B)") (class "Default")
      (node (ref "R32") (pin "2") (pinfunction "2_2") (pintype "passive"))
      (node (ref "T22") (pin "2") (pinfunction "B_2") (pintype "passive"))
    )
    (net (code "48") (name "Net-(T22-C)") (class "Default")
      (node (ref "R33") (pin "1") (pinfunction "1_1") (pintype "passive"))
      (node (ref "R34") (pin "1") (pinfunction "1_1") (pintype "passive"))
      (node (ref "T22") (pin "1") (pinfunction "C_1") (pintype "passive"))
    )
    (net (code "49") (name "Net-(T23-B)") (class "Default")
      (node (ref "R33") (pin "2") (pinfunction "2_2") (pintype "passive"))
      (node (ref "T23") (pin "2") (pinfunction "B_2") (pintype "passive"))
    )
    (net (code "50") (name "Net-(T24-B)") (class "Default")
      (node (ref "R35") (pin "2") (pinfunction "2_2") (pintype "passive"))
      (node (ref "T24") (pin "2") (pinfunction "B_2") (pintype "passive"))
    )
    (net (code "51") (name "Net-(T24-C)") (class "Default")
      (node (ref "R37") (pin "1") (pinfunction "1_1") (pintype "passive"))
      (node (ref "R40") (pin "1") (pinfunction "1_1") (pintype "passive"))
      (node (ref "T24") (pin "1") (pinfunction "C_1") (pintype "passive"))
    )
    (net (code "52") (name "Net-(T25-B)") (class "Default")
      (node (ref "R36") (pin "2") (pinfunction "2_2") (pintype "passive"))
      (node (ref "T25") (pin "2") (pinfunction "B_2") (pintype "passive"))
    )
    (net (code "53") (name "Net-(T26-B)") (class "Default")
      (node (ref "R39") (pin "2") (pinfunction "2_2") (pintype "passive"))
      (node (ref "T26") (pin "2") (pinfunction "B_2") (pintype "passive"))
    )
    (net (code "54") (name "Net-(T26-C)") (class "Default")
      (node (ref "R36") (pin "1") (pinfunction "1_1") (pintype "passive"))
      (node (ref "R41") (pin "1") (pinfunction "1_1") (pintype "passive"))
      (node (ref "R46") (pin "1") (pinfunction "1_1") (pintype "passive"))
      (node (ref "R59") (pin "1") (pinfunction "1_1") (pintype "passive"))
      (node (ref "R7") (pin "1") (pinfunction "1_1") (pintype "passive"))
      (node (ref "T26") (pin "1") (pinfunction "C_1") (pintype "passive"))
      (node (ref "T27") (pin "1") (pinfunction "C_1") (pintype "passive"))
    )
    (net (code "55") (name "Net-(T27-B)") (class "Default")
      (node (ref "R40") (pin "2") (pinfunction "2_2") (pintype "passive"))
      (node (ref "T27") (pin "2") (pinfunction "B_2") (pintype "passive"))
    )
    (net (code "56") (name "Net-(T28-B)") (class "Default")
      (node (ref "R42") (pin "2") (pinfunction "2_2") (pintype "passive"))
      (node (ref "T28") (pin "2") (pinfunction "B_2") (pintype "passive"))
    )
    (net (code "57") (name "Net-(T28-C)") (class "Default")
      (node (ref "R44") (pin "1") (pinfunction "1_1") (pintype "passive"))
      (node (ref "R53") (pin "1") (pinfunction "1_1") (pintype "passive"))
      (node (ref "T28") (pin "1") (pinfunction "C_1") (pintype "passive"))
    )
    (net (code "58") (name "Net-(T28-E)") (class "Default")
      (node (ref "T28") (pin "3") (pinfunction "E_3") (pintype "passive"))
      (node (ref "T29") (pin "1") (pinfunction "C_1") (pintype "passive"))
    )
    (net (code "59") (name "Net-(T29-B)") (class "Default")
      (node (ref "R43") (pin "2") (pinfunction "2_2") (pintype "passive"))
      (node (ref "T29") (pin "2") (pinfunction "B_2") (pintype "passive"))
    )
    (net (code "60") (name "Net-(T30-B)") (class "Default")
      (node (ref "R45") (pin "2") (pinfunction "2_2") (pintype "passive"))
      (node (ref "T30") (pin "2") (pinfunction "B_2") (pintype "passive"))
    )
    (net (code "61") (name "Net-(T30-C)") (class "Default")
      (node (ref "R47") (pin "1") (pinfunction "1_1") (pintype "passive"))
      (node (ref "R51") (pin "1") (pinfunction "1_1") (pintype "passive"))
      (node (ref "T30") (pin "1") (pinfunction "C_1") (pintype "passive"))
    )
    (net (code "62") (name "Net-(T30-E)") (class "Default")
      (node (ref "T30") (pin "3") (pinfunction "E_3") (pintype "passive"))
      (node (ref "T31") (pin "1") (pinfunction "C_1") (pintype "passive"))
    )
    (net (code "63") (name "Net-(T31-B)") (class "Default")
      (node (ref "R46") (pin "2") (pinfunction "2_2") (pintype "passive"))
      (node (ref "T31") (pin "2") (pinfunction "B_2") (pintype "passive"))
    )
    (net (code "64") (name "Net-(T32-B)") (class "Default")
      (node (ref "R48") (pin "2") (pinfunction "2_2") (pintype "passive"))
      (node (ref "T32") (pin "2") (pinfunction "B_2") (pintype "passive"))
    )
    (net (code "65") (name "Net-(T32-C)") (class "Default")
      (node (ref "R50") (pin "1") (pinfunction "1_1") (pintype "passive"))
      (node (ref "T32") (pin "1") (pinfunction "C_1") (pintype "passive"))
    )
    (net (code "66") (name "Net-(T33-B)") (class "Default")
      (node (ref "R49") (pin "2") (pinfunction "2_2") (pintype "passive"))
      (node (ref "T33") (pin "2") (pinfunction "B_2") (pintype "passive"))
    )
    (net (code "67") (name "Net-(T34-B)") (class "Default")
      (node (ref "R51") (pin "2") (pinfunction "2_2") (pintype "passive"))
      (node (ref "T34") (pin "2") (pinfunction "B_2") (pintype "passive"))
    )
    (net (code "68") (name "Net-(T34-C)") (class "Default")
      (node (ref "R49") (pin "1") (pinfunction "1_1") (pintype "passive"))
      (node (ref "R52") (pin "1") (pinfunction "1_1") (pintype "passive"))
      (node (ref "T34") (pin "1") (pinfunction "C_1") (pintype "passive"))
    )
    (net (code "69") (name "Net-(T35-B)") (class "Default")
      (node (ref "R53") (pin "2") (pinfunction "2_2") (pintype "passive"))
      (node (ref "T35") (pin "2") (pinfunction "B_2") (pintype "passive"))
    )
    (net (code "70") (name "Net-(T35-C)") (class "Default")
      (node (ref "R48") (pin "1") (pinfunction "1_1") (pintype "passive"))
      (node (ref "R54") (pin "1") (pinfunction "1_1") (pintype "passive"))
      (node (ref "T35") (pin "1") (pinfunction "C_1") (pintype "passive"))
    )
    (net (code "71") (name "Net-(T36-B)") (class "Default")
      (node (ref "R55") (pin "2") (pinfunction "2_2") (pintype "passive"))
      (node (ref "T36") (pin "2") (pinfunction "B_2") (pintype "passive"))
    )
    (net (code "72") (name "Net-(T36-C)") (class "Default")
      (node (ref "R57") (pin "1") (pinfunction "1_1") (pintype "passive"))
      (node (ref "R63") (pin "1") (pinfunction "1_1") (pintype "passive"))
      (node (ref "T36") (pin "1") (pinfunction "C_1") (pintype "passive"))
    )
    (net (code "73") (name "Net-(T36-E)") (class "Default")
      (node (ref "T36") (pin "3") (pinfunction "E_3") (pintype "passive"))
      (node (ref "T37") (pin "1") (pinfunction "C_1") (pintype "passive"))
    )
    (net (code "74") (name "Net-(T37-B)") (class "Default")
      (node (ref "R56") (pin "2") (pinfunction "2_2") (pintype "passive"))
      (node (ref "T37") (pin "2") (pinfunction "B_2") (pintype "passive"))
    )
    (net (code "75") (name "Net-(T38-B)") (class "Default")
      (node (ref "R58") (pin "2") (pinfunction "2_2") (pintype "passive"))
      (node (ref "T38") (pin "2") (pinfunction "B_2") (pintype "passive"))
    )
    (net (code "76") (name "Net-(T38-C)") (class "Default")
      (node (ref "R60") (pin "1") (pinfunction "1_1") (pintype "passive"))
      (node (ref "R61") (pin "1") (pinfunction "1_1") (pintype "passive"))
      (node (ref "T38") (pin "1") (pinfunction "C_1") (pintype "passive"))
    )
    (net (code "77") (name "Net-(T38-E)") (class "Default")
      (node (ref "T38") (pin "3") (pinfunction "E_3") (pintype "passive"))
      (node (ref "T39") (pin "1") (pinfunction "C_1") (pintype "passive"))
    )
    (net (code "78") (name "Net-(T39-B)") (class "Default")
      (node (ref "R59") (pin "2") (pinfunction "2_2") (pintype "passive"))
      (node (ref "T39") (pin "2") (pinfunction "B_2") (pintype "passive"))
    )
    (net (code "79") (name "Net-(T40-B)") (class "Default")
      (node (ref "R61") (pin "2") (pinfunction "2_2") (pintype "passive"))
      (node (ref "T40") (pin "2") (pinfunction "B_2") (pintype "passive"))
    )
    (net (code "80") (name "Net-(T41-B)") (class "Default")
      (node (ref "R63") (pin "2") (pinfunction "2_2") (pintype "passive"))
      (node (ref "T41") (pin "2") (pinfunction "B_2") (pintype "passive"))
    )
    (net (code "81") (name "Net-(T42-B)") (class "Default")
      (node (ref "R65") (pin "2") (pinfunction "2_2") (pintype "passive"))
      (node (ref "T42") (pin "2") (pinfunction "B_2") (pintype "passive"))
    )
    (net (code "82") (name "Net-(T42-C)") (class "Default")
      (node (ref "R27") (pin "1") (pinfunction "1_1") (pintype "passive"))
      (node (ref "R30") (pin "1") (pinfunction "1_1") (pintype "passive"))
      (node (ref "R67") (pin "1") (pinfunction "1_1") (pintype "passive"))
      (node (ref "T42") (pin "1") (pinfunction "C_1") (pintype "passive"))
      (node (ref "T43") (pin "1") (pinfunction "C_1") (pintype "passive"))
      (node (ref "T44") (pin "1") (pinfunction "C_1") (pintype "passive"))
    )
    (net (code "83") (name "Net-(T43-B)") (class "Default")
      (node (ref "R66") (pin "2") (pinfunction "2_2") (pintype "passive"))
      (node (ref "T43") (pin "2") (pinfunction "B_2") (pintype "passive"))
    )
    (net (code "84") (name "Net-(T44-B)") (class "Default")
      (node (ref "R68") (pin "2") (pinfunction "2_2") (pintype "passive"))
      (node (ref "T44") (pin "2") (pinfunction "B_2") (pintype "passive"))
    )
    (net (code "85") (name "Net-(T45-B)") (class "Default")
      (node (ref "R69") (pin "2") (pinfunction "2_2") (pintype "passive"))
      (node (ref "T45") (pin "2") (pinfunction "B_2") (pintype "passive"))
    )
    (net (code "86") (name "Net-(T45-C)") (class "Default")
      (node (ref "R71") (pin "1") (pinfunction "1_1") (pintype "passive"))
      (node (ref "R73") (pin "1") (pinfunction "1_1") (pintype "passive"))
      (node (ref "T45") (pin "1") (pinfunction "C_1") (pintype "passive"))
      (node (ref "T46") (pin "1") (pinfunction "C_1") (pintype "passive"))
    )
    (net (code "87") (name "Net-(T46-B)") (class "Default")
      (node (ref "R70") (pin "2") (pinfunction "2_2") (pintype "passive"))
      (node (ref "T46") (pin "2") (pinfunction "B_2") (pintype "passive"))
    )
    (net (code "88") (name "Net-(T47-B)") (class "Default")
      (node (ref "R72") (pin "2") (pinfunction "2_2") (pintype "passive"))
      (node (ref "T47") (pin "2") (pinfunction "B_2") (pintype "passive"))
    )
    (net (code "89") (name "Net-(T47-C)") (class "Default")
      (node (ref "R5") (pin "1") (pinfunction "1_1") (pintype "passive"))
      (node (ref "R74") (pin "1") (pinfunction "1_1") (pintype "passive"))
      (node (ref "T47") (pin "1") (pinfunction "C_1") (pintype "passive"))
    )
    (net (code "90") (name "Net-(T48-B)") (class "Default")
      (node (ref "R73") (pin "2") (pinfunction "2_2") (pintype "passive"))
      (node (ref "T48") (pin "2") (pinfunction "B_2") (pintype "passive"))
    )
    (net (code "91") (name "Net-(T48-C)") (class "Default")
      (node (ref "R10") (pin "1") (pinfunction "1_1") (pintype "passive"))
      (node (ref "R68") (pin "1") (pinfunction "1_1") (pintype "passive"))
      (node (ref "R75") (pin "1") (pinfunction "1_1") (pintype "passive"))
      (node (ref "R8") (pin "1") (pinfunction "1_1") (pintype "passive"))
      (node (ref "T48") (pin "1") (pinfunction "C_1") (pintype "passive"))
    )
    (net (code "92") (name "Net-(T65-B)") (class "Default")
      (node (ref "R95") (pin "2") (pinfunction "2_2") (pintype "passive"))
      (node (ref "T65") (pin "2") (pinfunction "B_2") (pintype "passive"))
    )
    (net (code "93") (name "Net-(T65-C)") (class "Default")
      (node (ref "T65") (pin "1") (pinfunction "C_1") (pintype "passive"))
      (node (ref "VALUE") (pin "K") (pinfunction "C_K") (pintype "passive"))
    )
    (net (code "94") (name "OUT") (class "Default")
      (node (ref "T32") (pin "3") (pinfunction "E_3") (pintype "passive"))
      (node (ref "T33") (pin "1") (pinfunction "C_1") (pintype "passive"))
      (node (ref "X3") (pin "4") (pinfunction "S_4") (pintype "passive"))
    )
    (net (code "95") (name "RESET") (class "Default")
      (node (ref "R23") (pin "1") (pinfunction "1_1") (pintype "passive"))
      (node (ref "R66") (pin "1") (pinfunction "1_1") (pintype "passive"))
      (node (ref "X2") (pin "4") (pinfunction "S_4") (pintype "passive"))
    )
    (net (code "96") (name "UP") (class "Default")
      (node (ref "R55") (pin "1") (pinfunction "1_1") (pintype "passive"))
      (node (ref "R69") (pin "1") (pinfunction "1_1") (pintype "passive"))
      (node (ref "X2") (pin "5") (pinfunction "S_5") (pintype "passive"))
    )
    (net (code "97") (name "VALUE") (class "Default")
      (node (ref "R11") (pin "1") (pinfunction "1_1") (pintype "passive"))
      (node (ref "R38") (pin "1") (pinfunction "1_1") (pintype "passive"))
      (node (ref "R39") (pin "1") (pinfunction "1_1") (pintype "passive"))
      (node (ref "R42") (pin "1") (pinfunction "1_1") (pintype "passive"))
      (node (ref "R56") (pin "1") (pinfunction "1_1") (pintype "passive"))
      (node (ref "R95") (pin "1") (pinfunction "1_1") (pintype "passive"))
      (node (ref "T23") (pin "1") (pinfunction "C_1") (pintype "passive"))
      (node (ref "T25") (pin "1") (pinfunction "C_1") (pintype "passive"))
      (node (ref "X3") (pin "5") (pinfunction "S_5") (pintype "passive"))
    )
    (net (code "98") (name "VCC") (class "Default")
      (node (ref "R12") (pin "2") (pinfunction "2_2") (pintype "passive"))
      (node (ref "R15") (pin "2") (pinfunction "2_2") (pintype "passive"))
      (node (ref "R18") (pin "2") (pinfunction "2_2") (pintype "passive"))
      (node (ref "R21") (pin "2") (pinfunction "2_2") (pintype "passive"))
      (node (ref "R24") (pin "2") (pinfunction "2_2") (pintype "passive"))
      (node (ref "R28") (pin "2") (pinfunction "2_2") (pintype "passive"))
      (node (ref "R3") (pin "2") (pinfunction "2_2") (pintype "passive"))
      (node (ref "R31") (pin "2") (pinfunction "2_2") (pintype "passive"))
      (node (ref "R34") (pin "2") (pinfunction "2_2") (pintype "passive"))
      (node (ref "R37") (pin "2") (pinfunction "2_2") (pintype "passive"))
      (node (ref "R38") (pin "2") (pinfunction "2_2") (pintype "passive"))
      (node (ref "R41") (pin "2") (pinfunction "2_2") (pintype "passive"))
      (node (ref "R44") (pin "2") (pinfunction "2_2") (pintype "passive"))
      (node (ref "R47") (pin "2") (pinfunction "2_2") (pintype "passive"))
      (node (ref "R50") (pin "2") (pinfunction "2_2") (pintype "passive"))
      (node (ref "R52") (pin "2") (pinfunction "2_2") (pintype "passive"))
      (node (ref "R54") (pin "2") (pinfunction "2_2") (pintype "passive"))
      (node (ref "R57") (pin "2") (pinfunction "2_2") (pintype "passive"))
      (node (ref "R6") (pin "2") (pinfunction "2_2") (pintype "passive"))
      (node (ref "R60") (pin "2") (pinfunction "2_2") (pintype "passive"))
      (node (ref "R62") (pin "2") (pinfunction "2_2") (pintype "passive"))
      (node (ref "R64") (pin "2") (pinfunction "2_2") (pintype "passive"))
      (node (ref "R67") (pin "2") (pinfunction "2_2") (pintype "passive"))
      (node (ref "R71") (pin "2") (pinfunction "2_2") (pintype "passive"))
      (node (ref "R74") (pin "2") (pinfunction "2_2") (pintype "passive"))
      (node (ref "R75") (pin "2") (pinfunction "2_2") (pintype "passive"))
      (node (ref "R9") (pin "2") (pinfunction "2_2") (pintype "passive"))
      (node (ref "R96") (pin "2") (pinfunction "2_2") (pintype "passive"))
      (node (ref "X2") (pin "1") (pinfunction "S_1") (pintype "passive"))
    )
    (net (code "99") (name "WE") (class "Default")
      (node (ref "R43") (pin "1") (pinfunction "1_1") (pintype "passive"))
      (node (ref "R45") (pin "1") (pinfunction "1_1") (pintype "passive"))
      (node (ref "X3") (pin "3") (pinfunction "S_3") (pintype "passive"))
    )
  )
)
